# senseBox-SCD30_V20.net
KiCad netlist of a schematic drawn in EAGLE
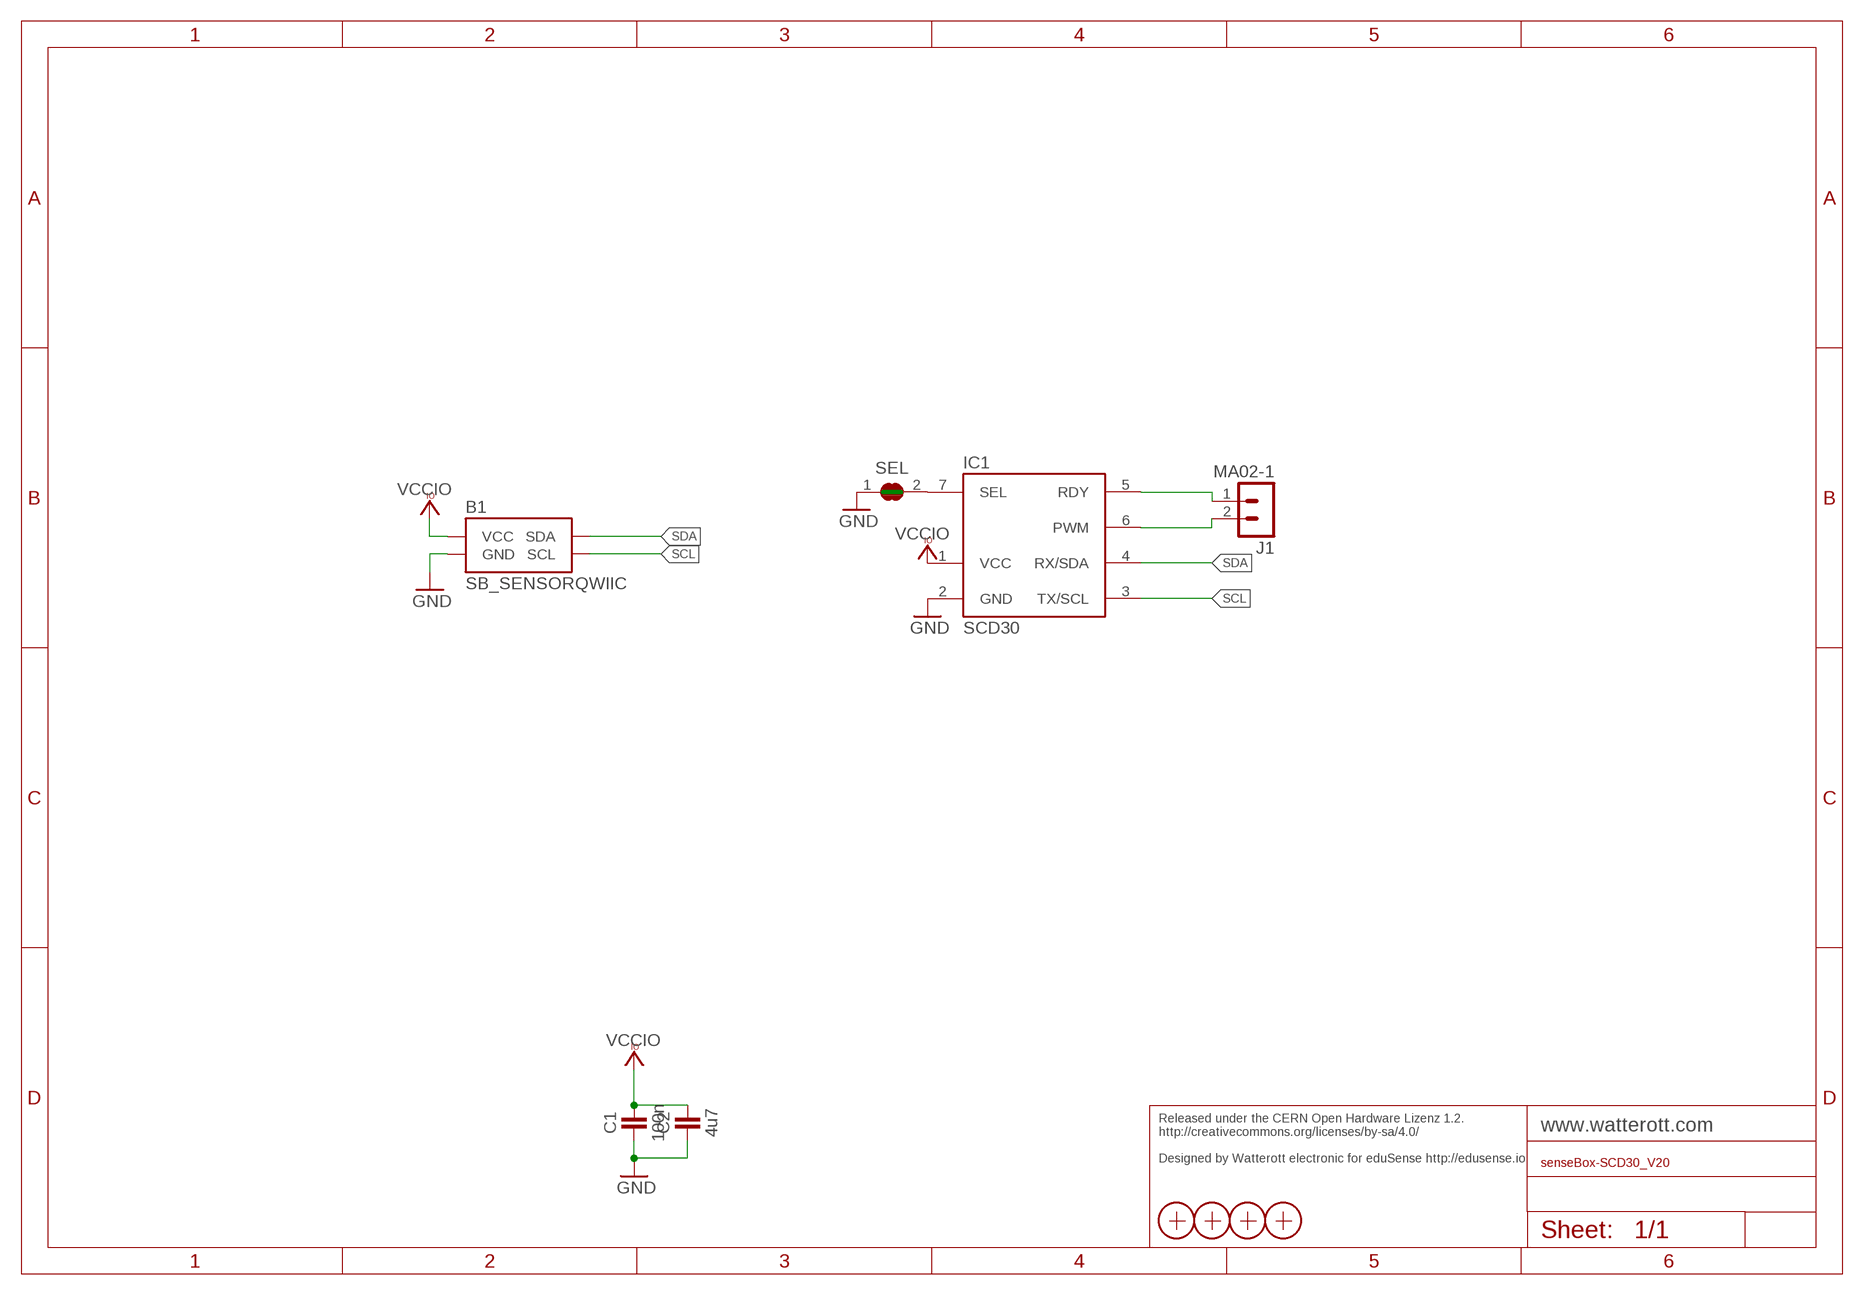
[diagram p0: schematic, sheet 1]

(export (version "E")
  (design (tool "Eeschema 10.0.6"))
  (components
    (comp (ref "B1")
      (value "SB_SENSORQWIIC")
      (footprint "eagle-import:SB-45X25_QWIIC")
      (libsource (lib "eagle-import") (part "SB_SENSORQWIIC"))
    )
    (comp (ref "C1")
      (value "100n")
      (footprint "eagle-import:C0402")
      (libsource (lib "eagle-import") (part "CAPACITOR-0402"))
    )
    (comp (ref "C2")
      (value "4u7")
      (footprint "eagle-import:C0402")
      (libsource (lib "eagle-import") (part "CAPACITOR-0402"))
    )
    (comp (ref "IC1")
      (value "SCD30")
      (footprint "eagle-import:SCD30")
      (libsource (lib "eagle-import") (part "SCD30"))
    )
    (comp (ref "J1")
      (value "MA02-1")
      (footprint "eagle-import:MA02-1")
      (libsource (lib "eagle-import") (part "MA02-1"))
    )
    (comp (ref "SEL")
      (value "JUMPER2-0402-NC")
      (footprint "eagle-import:JUMPER2-0402_NC")
      (libsource (lib "eagle-import") (part "JUMPER2-0402-NC"))
    )
    (comp (ref "X1")
      (value "PASSER-07")
      (footprint "eagle-import:PASSER_07MM")
      (libsource (lib "eagle-import") (part "PASSER-07"))
    )
    (comp (ref "X2")
      (value "PASSER-07")
      (footprint "eagle-import:PASSER_07MM")
      (libsource (lib "eagle-import") (part "PASSER-07"))
    )
    (comp (ref "X3")
      (value "PASSER-07")
      (footprint "eagle-import:PASSER_07MM")
      (libsource (lib "eagle-import") (part "PASSER-07"))
    )
    (comp (ref "X4")
      (value "PASSER-07")
      (footprint "eagle-import:PASSER_07MM")
      (libsource (lib "eagle-import") (part "PASSER-07"))
    )
  )
  (nets
    (net (code "1") (name "GND") (class "Default")
      (node (ref "B1") (pin "GND") (pinfunction "GND_GND") (pintype "power_in"))
      (node (ref "B1") (pin "GND1") (pinfunction "GND_GND1") (pintype "power_in"))
      (node (ref "B1") (pin "GND2") (pinfunction "GND_GND2") (pintype "power_in"))
      (node (ref "B1") (pin "SHLD1") (pinfunction "GND_SHLD1") (pintype "power_in"))
      (node (ref "B1") (pin "SHLD2") (pinfunction "GND_SHLD2") (pintype "power_in"))
      (node (ref "B1") (pin "SHLD3") (pinfunction "GND_SHLD3") (pintype "power_in"))
      (node (ref "B1") (pin "SHLD4") (pinfunction "GND_SHLD4") (pintype "power_in"))
      (node (ref "B1") (pin "SHLD5") (pinfunction "GND_SHLD5") (pintype "power_in"))
      (node (ref "B1") (pin "SHLD6") (pinfunction "GND_SHLD6") (pintype "power_in"))
      (node (ref "C1") (pin "1") (pinfunction "1_1") (pintype "passive"))
      (node (ref "C2") (pin "1") (pinfunction "1_1") (pintype "passive"))
      (node (ref "IC1") (pin "2") (pinfunction "GND_2") (pintype "power_in"))
      (node (ref "SEL") (pin "1") (pinfunction "1_1") (pintype "passive"))
    )
    (net (code "2") (name "Net-(IC1-PWM)") (class "Default")
      (node (ref "IC1") (pin "6") (pinfunction "PWM_6") (pintype "bidirectional"))
      (node (ref "J1") (pin "2") (pinfunction "2_2") (pintype "passive"))
    )
    (net (code "3") (name "Net-(IC1-RDY)") (class "Default")
      (node (ref "IC1") (pin "5") (pinfunction "RDY_5") (pintype "bidirectional"))
      (node (ref "J1") (pin "1") (pinfunction "1_1") (pintype "passive"))
    )
    (net (code "4") (name "Net-(IC1-SEL)") (class "Default")
      (node (ref "IC1") (pin "7") (pinfunction "SEL_7") (pintype "bidirectional"))
      (node (ref "SEL") (pin "2") (pinfunction "2_2") (pintype "passive"))
    )
    (net (code "5") (name "SCL") (class "Default")
      (node (ref "B1") (pin "SCL") (pinfunction "SCL_SCL") (pintype "bidirectional"))
      (node (ref "B1") (pin "SCL1") (pinfunction "SCL_SCL1") (pintype "bidirectional"))
      (node (ref "B1") (pin "SCL2") (pinfunction "SCL_SCL2") (pintype "bidirectional"))
      (node (ref "IC1") (pin "3") (pinfunction "TX/SCL_3") (pintype "bidirectional"))
    )
    (net (code "6") (name "SDA") (class "Default")
      (node (ref "B1") (pin "SDA") (pinfunction "SDA_SDA") (pintype "bidirectional"))
      (node (ref "B1") (pin "SDA1") (pinfunction "SDA_SDA1") (pintype "bidirectional"))
      (node (ref "B1") (pin "SDA2") (pinfunction "SDA_SDA2") (pintype "bidirectional"))
      (node (ref "IC1") (pin "4") (pinfunction "RX/SDA_4") (pintype "bidirectional"))
    )
    (net (code "7") (name "VCCIO") (class "Default")
      (node (ref "B1") (pin "VCC") (pinfunction "VCC_VCC") (pintype "power_in"))
      (node (ref "B1") (pin "VCC1") (pinfunction "VCC_VCC1") (pintype "power_in"))
      (node (ref "B1") (pin "VCC2") (pinfunction "VCC_VCC2") (pintype "power_in"))
      (node (ref "C1") (pin "2") (pinfunction "2_2") (pintype "passive"))
      (node (ref "C2") (pin "2") (pinfunction "2_2") (pintype "passive"))
      (node (ref "IC1") (pin "1") (pinfunction "VCC_1") (pintype "power_in"))
    )
  )
)
